# motor_controller.net
KiCad netlist of a schematic drawn in EAGLE
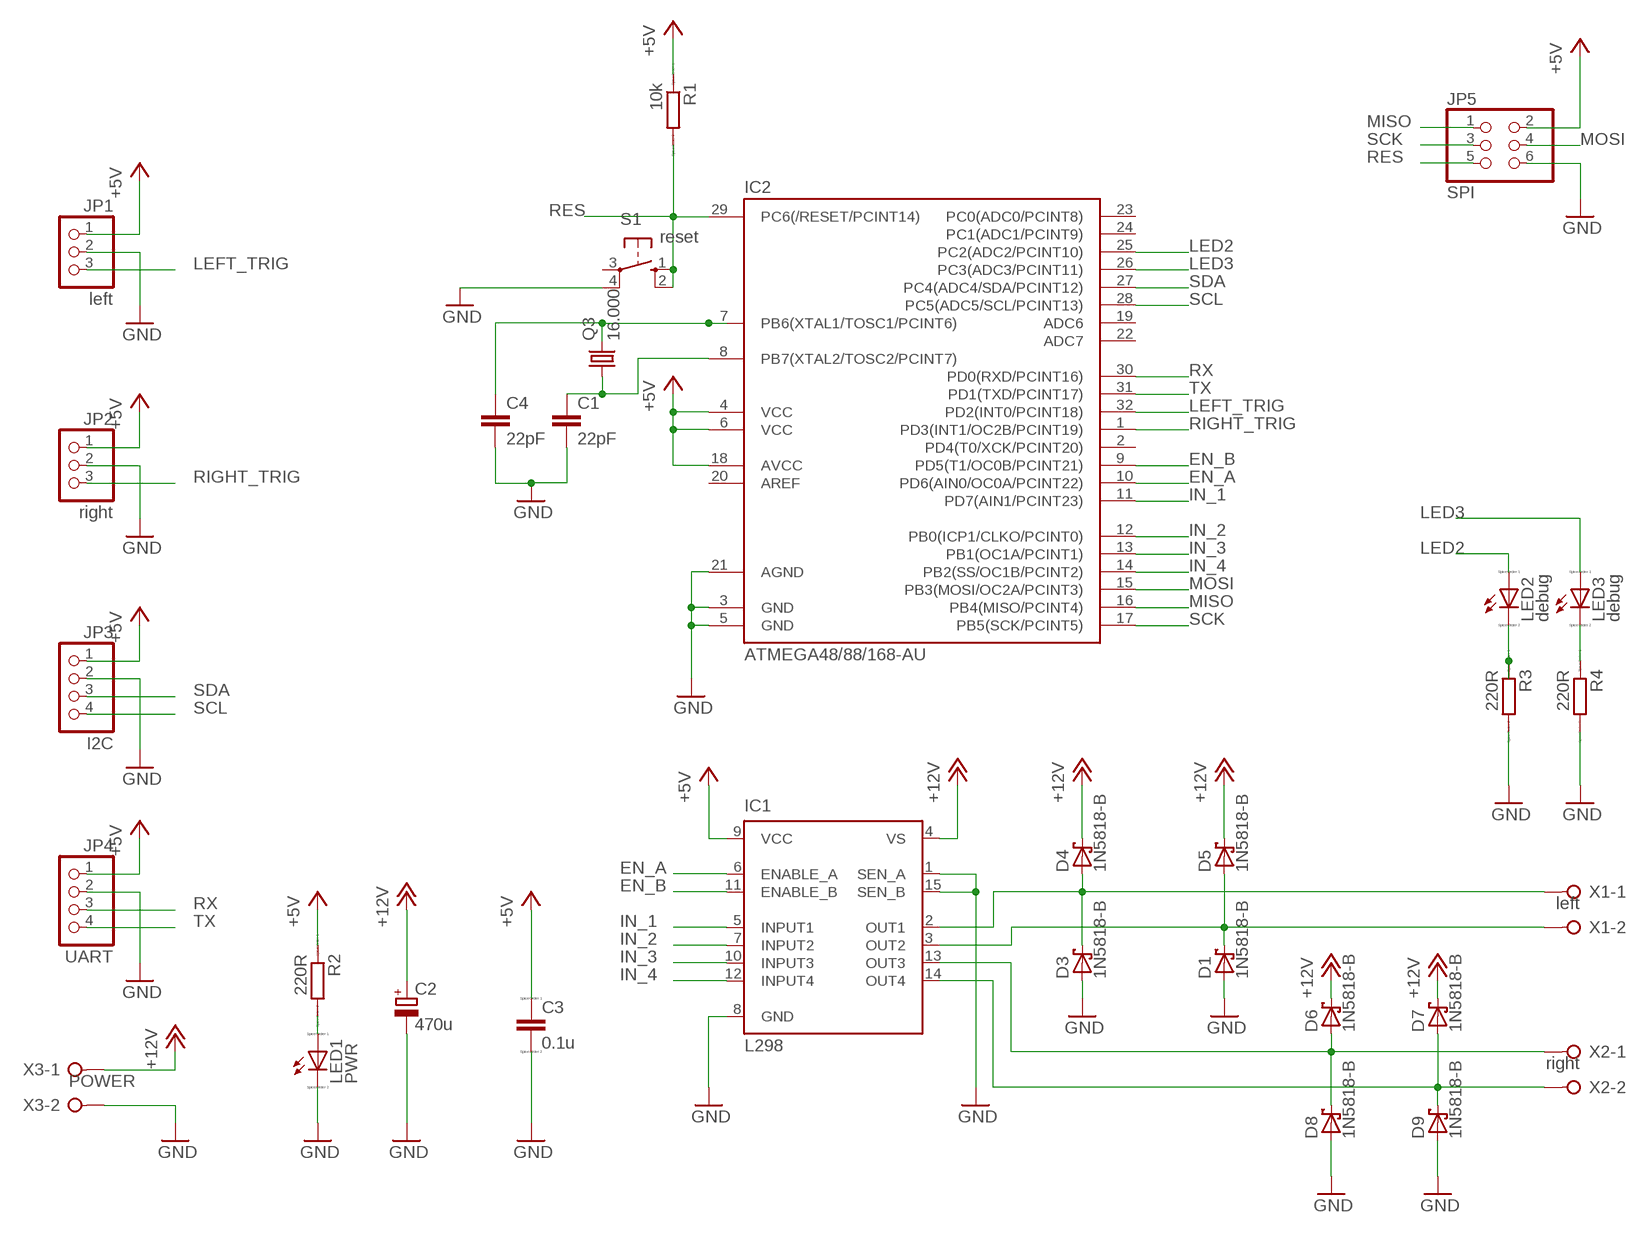
[diagram p0: schematic, sheet 1]

(export (version "E")
  (design (tool "Eeschema 10.0.6"))
  (components
    (comp (ref "C1")
      (value "22pF")
      (footprint "eagle-import:C0805")
      (libsource (lib "eagle-import") (part "C-EUC0805"))
    )
    (comp (ref "C2")
      (value "470u")
      (footprint "eagle-import:E5-10,5")
      (libsource (lib "eagle-import") (part "CPOL-EUE5-10.5"))
    )
    (comp (ref "C3")
      (value "0.1u")
      (footprint "eagle-import:C0805")
      (libsource (lib "eagle-import") (part "C"))
    )
    (comp (ref "C4")
      (value "22pF")
      (footprint "eagle-import:C0805")
      (libsource (lib "eagle-import") (part "C-EUC0805"))
    )
    (comp (ref "D1")
      (value "1N5818-B")
      (footprint "eagle-import:DO41-7.6")
      (libsource (lib "eagle-import") (part "1N5818-B"))
    )
    (comp (ref "D3")
      (value "1N5818-B")
      (footprint "eagle-import:DO41-7.6")
      (libsource (lib "eagle-import") (part "1N5818-B"))
    )
    (comp (ref "D4")
      (value "1N5818-B")
      (footprint "eagle-import:DO41-7.6")
      (libsource (lib "eagle-import") (part "1N5818-B"))
    )
    (comp (ref "D5")
      (value "1N5818-B")
      (footprint "eagle-import:DO41-7.6")
      (libsource (lib "eagle-import") (part "1N5818-B"))
    )
    (comp (ref "D6")
      (value "1N5818-B")
      (footprint "eagle-import:DO41-7.6")
      (libsource (lib "eagle-import") (part "1N5818-B"))
    )
    (comp (ref "D7")
      (value "1N5818-B")
      (footprint "eagle-import:DO41-7.6")
      (libsource (lib "eagle-import") (part "1N5818-B"))
    )
    (comp (ref "D8")
      (value "1N5818-B")
      (footprint "eagle-import:DO41-7.6")
      (libsource (lib "eagle-import") (part "1N5818-B"))
    )
    (comp (ref "D9")
      (value "1N5818-B")
      (footprint "eagle-import:DO41-7.6")
      (libsource (lib "eagle-import") (part "1N5818-B"))
    )
    (comp (ref "IC1")
      (value "L298")
      (footprint "eagle-import:MULTIWATT-15")
      (fields (field (name "MPN") "L298N"))
      (libsource (lib "eagle-import") (part "L298"))
    )
    (comp (ref "IC2")
      (value "ATMEGA48/88/168-AU")
      (footprint "eagle-import:TQFP32-08")
      (libsource (lib "eagle-import") (part "ATMEGA48/88/168-AU"))
    )
    (comp (ref "JP1")
      (value "left")
      (footprint "eagle-import:1X03")
      (libsource (lib "eagle-import") (part "PINHD-1X3"))
    )
    (comp (ref "JP2")
      (value "right")
      (footprint "eagle-import:1X03")
      (libsource (lib "eagle-import") (part "PINHD-1X3"))
    )
    (comp (ref "JP3")
      (value "I2C")
      (footprint "eagle-import:1X04")
      (libsource (lib "eagle-import") (part "PINHD-1X4"))
    )
    (comp (ref "JP4")
      (value "UART")
      (footprint "eagle-import:1X04")
      (libsource (lib "eagle-import") (part "PINHD-1X4"))
    )
    (comp (ref "JP5")
      (value "SPI")
      (footprint "eagle-import:2X03")
      (libsource (lib "eagle-import") (part "PINHD-2X3"))
    )
    (comp (ref "LED1")
      (value "PWR")
      (footprint "eagle-import:LED_1206")
      (libsource (lib "eagle-import") (part "LED_E"))
    )
    (comp (ref "LED2")
      (value "debug")
      (footprint "eagle-import:LED_1206")
      (libsource (lib "eagle-import") (part "LED_E"))
    )
    (comp (ref "LED3")
      (value "debug")
      (footprint "eagle-import:LED_1206")
      (libsource (lib "eagle-import") (part "LED_E"))
    )
    (comp (ref "Q3")
      (value "16.000")
      (footprint "eagle-import:HC49UP")
      (libsource (lib "eagle-import") (part "CRYSTALHC49UP"))
    )
    (comp (ref "R1")
      (value "10k")
      (footprint "eagle-import:R0805")
      (libsource (lib "eagle-import") (part "R"))
    )
    (comp (ref "R2")
      (value "220R")
      (footprint "eagle-import:R0805")
      (libsource (lib "eagle-import") (part "R"))
    )
    (comp (ref "R3")
      (value "220R")
      (footprint "eagle-import:R0805")
      (libsource (lib "eagle-import") (part "R"))
    )
    (comp (ref "R4")
      (value "220R")
      (footprint "eagle-import:R0805")
      (libsource (lib "eagle-import") (part "R"))
    )
    (comp (ref "S1")
      (value "reset")
      (footprint "eagle-import:B3F-10XX")
      (fields (field (name "MPN") "B3F-1000"))
      (libsource (lib "eagle-import") (part "10-XX"))
    )
    (comp (ref "X1")
      (value "left")
      (footprint "eagle-import:W237-132")
      (libsource (lib "eagle-import") (part "W237-02P"))
    )
    (comp (ref "X2")
      (value "right")
      (footprint "eagle-import:W237-132")
      (libsource (lib "eagle-import") (part "W237-02P"))
    )
    (comp (ref "X3")
      (value "POWER")
      (footprint "eagle-import:W237-132")
      (libsource (lib "eagle-import") (part "W237-02P"))
    )
  )
  (nets
    (net (code "1") (name "+5V") (class "Default")
      (node (ref "C3") (pin "1") (pinfunction "1_1") (pintype "passive"))
      (node (ref "IC1") (pin "9") (pinfunction "VCC_9") (pintype "power_in"))
      (node (ref "IC2") (pin "18") (pinfunction "AVCC_18") (pintype "passive"))
      (node (ref "IC2") (pin "4") (pinfunction "VCC_4") (pintype "power_in"))
      (node (ref "IC2") (pin "6") (pinfunction "VCC_6") (pintype "power_in"))
      (node (ref "JP1") (pin "1") (pinfunction "1_1") (pintype "passive"))
      (node (ref "JP2") (pin "1") (pinfunction "1_1") (pintype "passive"))
      (node (ref "JP3") (pin "1") (pinfunction "1_1") (pintype "passive"))
      (node (ref "JP4") (pin "1") (pinfunction "1_1") (pintype "passive"))
      (node (ref "JP5") (pin "2") (pinfunction "2_2") (pintype "passive"))
      (node (ref "R1") (pin "1") (pinfunction "1_1") (pintype "passive"))
      (node (ref "R2") (pin "1") (pinfunction "1_1") (pintype "passive"))
    )
    (net (code "2") (name "+12V") (class "Default")
      (node (ref "C2") (pin "+") (pinfunction "+_+") (pintype "passive"))
      (node (ref "D4") (pin "C") (pinfunction "C_C") (pintype "passive"))
      (node (ref "D5") (pin "C") (pinfunction "C_C") (pintype "passive"))
      (node (ref "D6") (pin "C") (pinfunction "C_C") (pintype "passive"))
      (node (ref "D7") (pin "C") (pinfunction "C_C") (pintype "passive"))
      (node (ref "IC1") (pin "4") (pinfunction "VS_4") (pintype "power_in"))
      (node (ref "X3") (pin "1") (pinfunction "KL_1") (pintype "passive"))
    )
    (net (code "3") (name "/EN_A") (class "Default")
      (node (ref "IC1") (pin "6") (pinfunction "ENABLE_A_6") (pintype "input"))
      (node (ref "IC2") (pin "10") (pinfunction "PD6(AIN0/OC0A/PCINT22)_10") (pintype "bidirectional"))
    )
    (net (code "4") (name "/EN_B") (class "Default")
      (node (ref "IC1") (pin "11") (pinfunction "ENABLE_B_11") (pintype "input"))
      (node (ref "IC2") (pin "9") (pinfunction "PD5(T1/OC0B/PCINT21)_9") (pintype "bidirectional"))
    )
    (net (code "5") (name "/IN_1") (class "Default")
      (node (ref "IC1") (pin "5") (pinfunction "INPUT1_5") (pintype "input"))
      (node (ref "IC2") (pin "11") (pinfunction "PD7(AIN1/PCINT23)_11") (pintype "bidirectional"))
    )
    (net (code "6") (name "/IN_2") (class "Default")
      (node (ref "IC1") (pin "7") (pinfunction "INPUT2_7") (pintype "input"))
      (node (ref "IC2") (pin "12") (pinfunction "PB0(ICP1/CLKO/PCINT0)_12") (pintype "bidirectional"))
    )
    (net (code "7") (name "/IN_3") (class "Default")
      (node (ref "IC1") (pin "10") (pinfunction "INPUT3_10") (pintype "input"))
      (node (ref "IC2") (pin "13") (pinfunction "PB1(OC1A/PCINT1)_13") (pintype "bidirectional"))
    )
    (net (code "8") (name "/IN_4") (class "Default")
      (node (ref "IC1") (pin "12") (pinfunction "INPUT4_12") (pintype "input"))
      (node (ref "IC2") (pin "14") (pinfunction "PB2(SS/OC1B/PCINT2)_14") (pintype "bidirectional"))
    )
    (net (code "9") (name "/LED2") (class "Default")
      (node (ref "IC2") (pin "25") (pinfunction "PC2(ADC2/PCINT10)_25") (pintype "bidirectional"))
      (node (ref "LED2") (pin "A") (pinfunction "A_A") (pintype "passive"))
    )
    (net (code "10") (name "/LED3") (class "Default")
      (node (ref "IC2") (pin "26") (pinfunction "PC3(ADC3/PCINT11)_26") (pintype "bidirectional"))
      (node (ref "LED3") (pin "A") (pinfunction "A_A") (pintype "passive"))
    )
    (net (code "11") (name "/LEFT_TRIG") (class "Default")
      (node (ref "IC2") (pin "32") (pinfunction "PD2(INT0/PCINT18)_32") (pintype "bidirectional"))
      (node (ref "JP1") (pin "3") (pinfunction "3_3") (pintype "passive"))
    )
    (net (code "12") (name "/MISO") (class "Default")
      (node (ref "IC2") (pin "16") (pinfunction "PB4(MISO/PCINT4)_16") (pintype "bidirectional"))
      (node (ref "JP5") (pin "1") (pinfunction "1_1") (pintype "passive"))
    )
    (net (code "13") (name "/MOSI") (class "Default")
      (node (ref "IC2") (pin "15") (pinfunction "PB3(MOSI/OC2A/PCINT3)_15") (pintype "bidirectional"))
      (node (ref "JP5") (pin "4") (pinfunction "4_4") (pintype "passive"))
    )
    (net (code "14") (name "/RES") (class "Default")
      (node (ref "IC2") (pin "29") (pinfunction "PC6(/RESET/PCINT14)_29") (pintype "bidirectional"))
      (node (ref "JP5") (pin "5") (pinfunction "5_5") (pintype "passive"))
      (node (ref "R1") (pin "2") (pinfunction "2_2") (pintype "passive"))
      (node (ref "S1") (pin "1") (pinfunction "S_1") (pintype "passive"))
      (node (ref "S1") (pin "2") (pinfunction "S1_2") (pintype "passive"))
    )
    (net (code "15") (name "/RIGHT_TRIG") (class "Default")
      (node (ref "IC2") (pin "1") (pinfunction "PD3(INT1/OC2B/PCINT19)_1") (pintype "bidirectional"))
      (node (ref "JP2") (pin "3") (pinfunction "3_3") (pintype "passive"))
    )
    (net (code "16") (name "/RX") (class "Default")
      (node (ref "IC2") (pin "30") (pinfunction "PD0(RXD/PCINT16)_30") (pintype "bidirectional"))
      (node (ref "JP4") (pin "3") (pinfunction "3_3") (pintype "passive"))
    )
    (net (code "17") (name "/SCK") (class "Default")
      (node (ref "IC2") (pin "17") (pinfunction "PB5(SCK/PCINT5)_17") (pintype "bidirectional"))
      (node (ref "JP5") (pin "3") (pinfunction "3_3") (pintype "passive"))
    )
    (net (code "18") (name "/SCL") (class "Default")
      (node (ref "IC2") (pin "28") (pinfunction "PC5(ADC5/SCL/PCINT13)_28") (pintype "bidirectional"))
      (node (ref "JP3") (pin "4") (pinfunction "4_4") (pintype "passive"))
    )
    (net (code "19") (name "/SDA") (class "Default")
      (node (ref "IC2") (pin "27") (pinfunction "PC4(ADC4/SDA/PCINT12)_27") (pintype "bidirectional"))
      (node (ref "JP3") (pin "3") (pinfunction "3_3") (pintype "passive"))
    )
    (net (code "20") (name "/TX") (class "Default")
      (node (ref "IC2") (pin "31") (pinfunction "PD1(TXD/PCINT17)_31") (pintype "bidirectional"))
      (node (ref "JP4") (pin "4") (pinfunction "4_4") (pintype "passive"))
    )
    (net (code "21") (name "GND") (class "Default")
      (node (ref "C1") (pin "2") (pinfunction "2_2") (pintype "passive"))
      (node (ref "C2") (pin "-") (pinfunction "-_-") (pintype "passive"))
      (node (ref "C3") (pin "2") (pinfunction "2_2") (pintype "passive"))
      (node (ref "C4") (pin "2") (pinfunction "2_2") (pintype "passive"))
      (node (ref "D1") (pin "A") (pinfunction "A_A") (pintype "passive"))
      (node (ref "D3") (pin "A") (pinfunction "A_A") (pintype "passive"))
      (node (ref "D8") (pin "A") (pinfunction "A_A") (pintype "passive"))
      (node (ref "D9") (pin "A") (pinfunction "A_A") (pintype "passive"))
      (node (ref "IC1") (pin "1") (pinfunction "SEN_A_1") (pintype "input"))
      (node (ref "IC1") (pin "15") (pinfunction "SEN_B_15") (pintype "input"))
      (node (ref "IC1") (pin "8") (pinfunction "GND_8") (pintype "power_in"))
      (node (ref "IC2") (pin "21") (pinfunction "AGND_21") (pintype "power_in"))
      (node (ref "IC2") (pin "3") (pinfunction "GND_3") (pintype "power_in"))
      (node (ref "IC2") (pin "5") (pinfunction "GND_5") (pintype "power_in"))
      (node (ref "JP1") (pin "2") (pinfunction "2_2") (pintype "passive"))
      (node (ref "JP2") (pin "2") (pinfunction "2_2") (pintype "passive"))
      (node (ref "JP3") (pin "2") (pinfunction "2_2") (pintype "passive"))
      (node (ref "JP4") (pin "2") (pinfunction "2_2") (pintype "passive"))
      (node (ref "JP5") (pin "6") (pinfunction "6_6") (pintype "passive"))
      (node (ref "LED1") (pin "C") (pinfunction "C_C") (pintype "passive"))
      (node (ref "R3") (pin "2") (pinfunction "2_2") (pintype "passive"))
      (node (ref "R4") (pin "2") (pinfunction "2_2") (pintype "passive"))
      (node (ref "S1") (pin "4") (pinfunction "P1_4") (pintype "passive"))
      (node (ref "X3") (pin "2") (pinfunction "KL_2") (pintype "passive"))
    )
    (net (code "22") (name "Net-(IC1-OUT1)") (class "Default")
      (node (ref "D3") (pin "C") (pinfunction "C_C") (pintype "passive"))
      (node (ref "D4") (pin "A") (pinfunction "A_A") (pintype "passive"))
      (node (ref "IC1") (pin "2") (pinfunction "OUT1_2") (pintype "output"))
      (node (ref "X1") (pin "1") (pinfunction "KL_1") (pintype "passive"))
    )
    (net (code "23") (name "Net-(IC1-OUT2)") (class "Default")
      (node (ref "D1") (pin "C") (pinfunction "C_C") (pintype "passive"))
      (node (ref "D5") (pin "A") (pinfunction "A_A") (pintype "passive"))
      (node (ref "IC1") (pin "3") (pinfunction "OUT2_3") (pintype "output"))
      (node (ref "X1") (pin "2") (pinfunction "KL_2") (pintype "passive"))
    )
    (net (code "24") (name "Net-(IC1-OUT3)") (class "Default")
      (node (ref "D6") (pin "A") (pinfunction "A_A") (pintype "passive"))
      (node (ref "D8") (pin "C") (pinfunction "C_C") (pintype "passive"))
      (node (ref "IC1") (pin "13") (pinfunction "OUT3_13") (pintype "output"))
      (node (ref "X2") (pin "1") (pinfunction "KL_1") (pintype "passive"))
    )
    (net (code "25") (name "Net-(IC1-OUT4)") (class "Default")
      (node (ref "D7") (pin "A") (pinfunction "A_A") (pintype "passive"))
      (node (ref "D9") (pin "C") (pinfunction "C_C") (pintype "passive"))
      (node (ref "IC1") (pin "14") (pinfunction "OUT4_14") (pintype "output"))
      (node (ref "X2") (pin "2") (pinfunction "KL_2") (pintype "passive"))
    )
    (net (code "26") (name "Net-(IC2-PB6(XTAL1{slash}TOSC1{slash}PCINT6))") (class "Default")
      (node (ref "C4") (pin "1") (pinfunction "1_1") (pintype "passive"))
      (node (ref "IC2") (pin "7") (pinfunction "PB6(XTAL1/TOSC1/PCINT6)_7") (pintype "bidirectional"))
      (node (ref "Q3") (pin "2") (pinfunction "2_2") (pintype "passive"))
    )
    (net (code "27") (name "Net-(IC2-PB7(XTAL2{slash}TOSC2{slash}PCINT7))") (class "Default")
      (node (ref "C1") (pin "1") (pinfunction "1_1") (pintype "passive"))
      (node (ref "IC2") (pin "8") (pinfunction "PB7(XTAL2/TOSC2/PCINT7)_8") (pintype "bidirectional"))
      (node (ref "Q3") (pin "1") (pinfunction "1_1") (pintype "passive"))
    )
    (net (code "28") (name "Net-(LED1-PadA)") (class "Default")
      (node (ref "LED1") (pin "A") (pinfunction "A_A") (pintype "passive"))
      (node (ref "R2") (pin "2") (pinfunction "2_2") (pintype "passive"))
    )
    (net (code "29") (name "Net-(LED2-PadC)") (class "Default")
      (node (ref "LED2") (pin "C") (pinfunction "C_C") (pintype "passive"))
      (node (ref "R3") (pin "1") (pinfunction "1_1") (pintype "passive"))
    )
    (net (code "30") (name "Net-(LED3-PadC)") (class "Default")
      (node (ref "LED3") (pin "C") (pinfunction "C_C") (pintype "passive"))
      (node (ref "R4") (pin "1") (pinfunction "1_1") (pintype "passive"))
    )
    (net (code "31") (name "unconnected-(IC2-ADC6-Pad19)") (class "Default")
      (node (ref "IC2") (pin "19") (pinfunction "ADC6_19") (pintype "passive"))
    )
    (net (code "32") (name "unconnected-(IC2-ADC7-Pad22)") (class "Default")
      (node (ref "IC2") (pin "22") (pinfunction "ADC7_22") (pintype "passive"))
    )
    (net (code "33") (name "unconnected-(IC2-AREF-Pad20)") (class "Default")
      (node (ref "IC2") (pin "20") (pinfunction "AREF_20") (pintype "passive"))
    )
    (net (code "34") (name "unconnected-(IC2-PC0(ADC0{slash}PCINT8)-Pad23)") (class "Default")
      (node (ref "IC2") (pin "23") (pinfunction "PC0(ADC0/PCINT8)_23") (pintype "bidirectional"))
    )
    (net (code "35") (name "unconnected-(IC2-PC1(ADC1{slash}PCINT9)-Pad24)") (class "Default")
      (node (ref "IC2") (pin "24") (pinfunction "PC1(ADC1/PCINT9)_24") (pintype "bidirectional"))
    )
    (net (code "36") (name "unconnected-(IC2-PD4(T0{slash}XCK{slash}PCINT20)-Pad2)") (class "Default")
      (node (ref "IC2") (pin "2") (pinfunction "PD4(T0/XCK/PCINT20)_2") (pintype "bidirectional"))
    )
    (net (code "37") (name "unconnected-(S1-P-Pad3)") (class "Default")
      (node (ref "S1") (pin "3") (pinfunction "P_3") (pintype "passive"))
    )
  )
)
